# RMP_MAIN_ZERO.net
KiCad netlist of a schematic drawn in Altium Designer
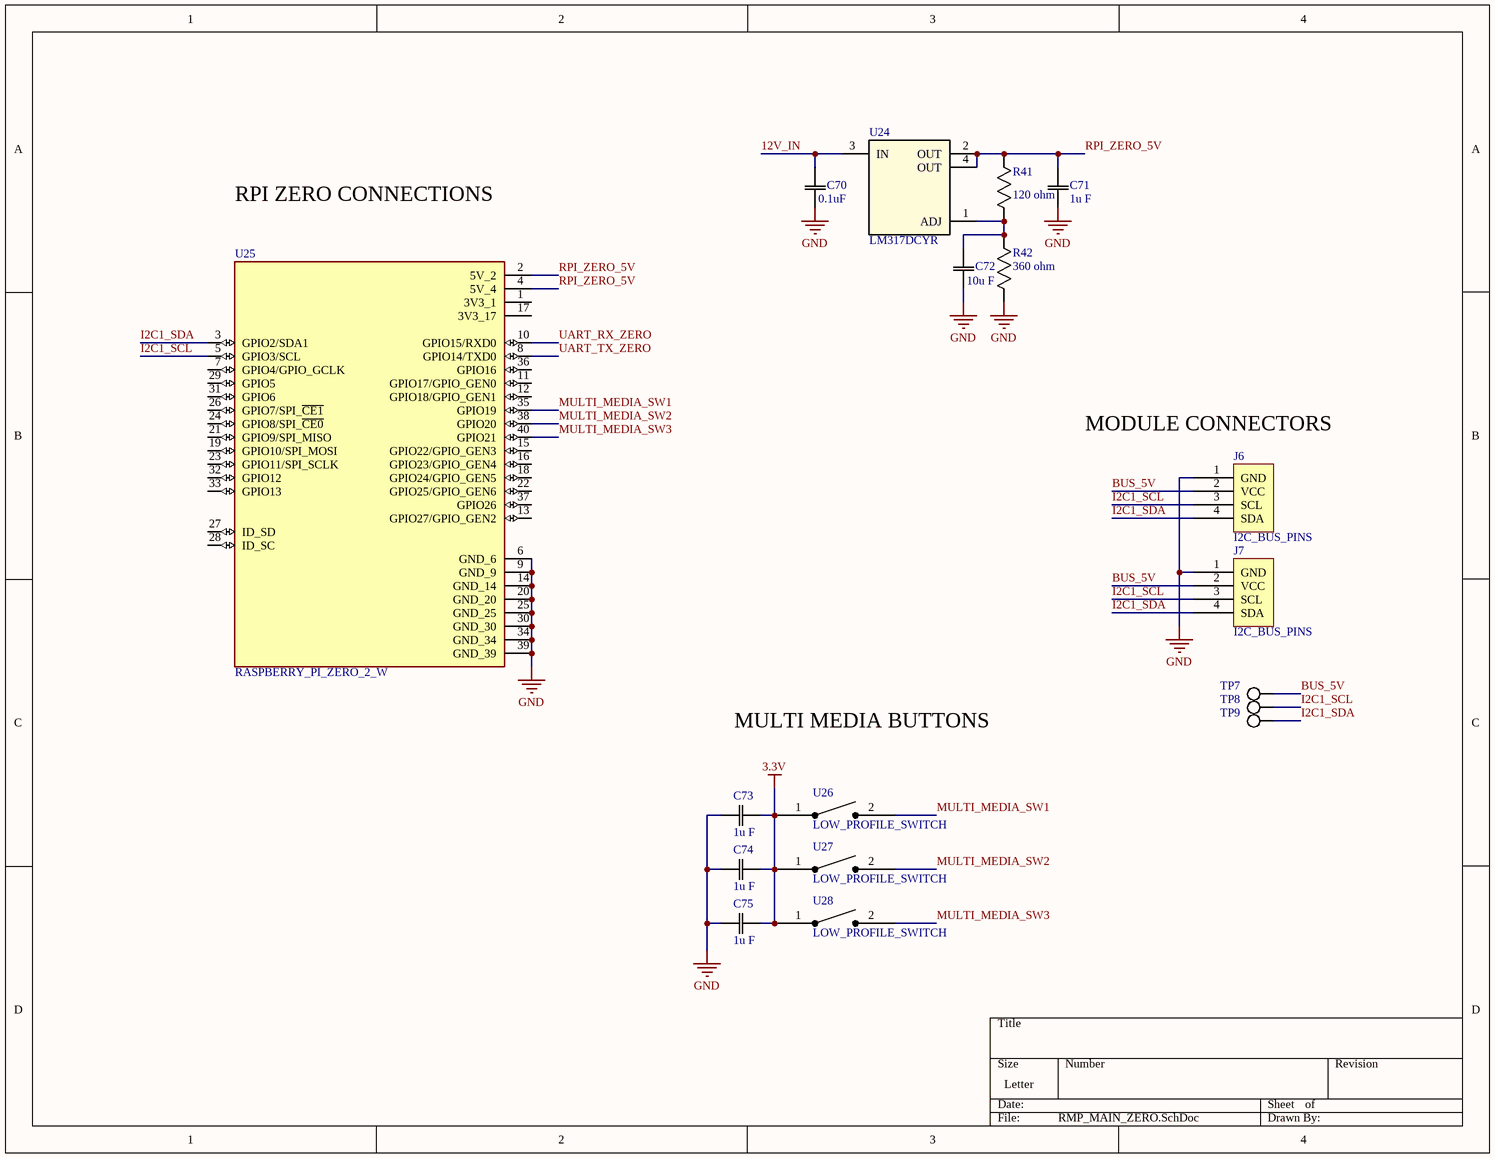
[diagram p0: RMP_MAIN_ZERO.SchDoc]

(export (version "E")
  (design (tool "Eeschema 10.0.6"))
  (components
    (comp (ref "C70")
      (value "0.1uF")
      (footprint "CC0805N_YAG-M")
      (description "0.1 µF ±10% 50V Ceramic Capacitor X7R 0805 (2012 Metric)")
      (fields (field (name "Comment") "CC0805KRX7R9BB104"))
      (libsource (lib "Schlib1") (part "CAP_CC0805KRX7R9BB104"))
    )
    (comp (ref "C71")
      (value "1u F")
      (footprint "CAP_CL21B105KAFNNNE_SAM-M")
      (description "1 µF ±10% 25V Ceramic Capacitor X7R 0805 (2012 Metric)")
      (fields (field (name "Comment") "CL21B105KAFNNNE"))
      (libsource (lib "Schlib1") (part "CAP_CL21B105KAFNNNE"))
    )
    (comp (ref "C72")
      (value "10u F")
      (footprint "G-21_MUR-M")
      (description "10 µF ±10% 16V Ceramic Capacitor X5R 0805 (2012 Metric)")
      (fields (field (name "Comment") "GRM21BR61C106KE15K"))
      (libsource (lib "Schlib1") (part "CAP_GRM21BR61C106KE15K"))
    )
    (comp (ref "C73")
      (value "1u F")
      (footprint "CAP_CL21B105KAFNNNE_SAM-M")
      (description "1 µF ±10% 25V Ceramic Capacitor X7R 0805 (2012 Metric)")
      (fields (field (name "Comment") "CL21B105KAFNNNE"))
      (libsource (lib "Schlib1") (part "CAP_CL21B105KAFNNNE"))
    )
    (comp (ref "C74")
      (value "1u F")
      (footprint "CAP_CL21B105KAFNNNE_SAM-M")
      (description "1 µF ±10% 25V Ceramic Capacitor X7R 0805 (2012 Metric)")
      (fields (field (name "Comment") "CL21B105KAFNNNE"))
      (libsource (lib "Schlib1") (part "CAP_CL21B105KAFNNNE"))
    )
    (comp (ref "C75")
      (value "1u F")
      (footprint "CAP_CL21B105KAFNNNE_SAM-M")
      (description "1 µF ±10% 25V Ceramic Capacitor X7R 0805 (2012 Metric)")
      (fields (field (name "Comment") "CL21B105KAFNNNE"))
      (libsource (lib "Schlib1") (part "CAP_CL21B105KAFNNNE"))
    )
    (comp (ref "J6")
      (value "I2C_BUS_PINS")
      (footprint "4 PIN HEADER")
      (libsource (lib "Schlib1") (part "I2C_BUS_PINS"))
    )
    (comp (ref "J7")
      (value "I2C_BUS_PINS")
      (footprint "4 PIN HEADER")
      (libsource (lib "Schlib1") (part "I2C_BUS_PINS"))
    )
    (comp (ref "R41")
      (value "120 ohm")
      (footprint "RES_RNCF0805_STP-M")
      (description "120 Ohms ±0.5% 0.25W, 1/4W Chip Resistor 0805 (2012 Metric) Automotive AEC-Q200 Thin Film")
      (fields (field (name "Comment") "RNCF0805DTE120R"))
      (libsource (lib "Schlib1") (part "RES_RNCF0805DTE120R"))
    )
    (comp (ref "R42")
      (value "360 ohm")
      (footprint "RES_RNCF0805_STP-M")
      (description "360 Ohms ±0.5% 0.25W, 1/4W Chip Resistor 0805 (2012 Metric) Automotive AEC-Q200 Thin Film")
      (fields (field (name "Comment") "RNCF0805DTE360R"))
      (libsource (lib "Schlib1") (part "RES_RNCF0805DTE360R"))
    )
    (comp (ref "TP7")
      (value "TestPoint")
      (footprint "Testpoint")
      (libsource (lib "Schlib1") (part "TestPoint"))
    )
    (comp (ref "TP8")
      (value "TestPoint")
      (footprint "Testpoint")
      (libsource (lib "Schlib1") (part "TestPoint"))
    )
    (comp (ref "TP9")
      (value "TestPoint")
      (footprint "Testpoint")
      (libsource (lib "Schlib1") (part "TestPoint"))
    )
    (comp (ref "U24")
      (value "LM317DCYR")
      (footprint "DCY0004A_M")
      (description "Linear Voltage Regulator IC Positive Adjustable 1 Output 1.5A SOT-223-4")
      (fields
        (field (name "ALTERNATE_PARTNUMBER") "LM317DCY")
        (field (name "MANUFACTURER") "Texas Instruments")
        (field (name "SYMBOLCREATER") "Altium")
      )
      (libsource (lib "Schlib1") (part "LM317DCYR"))
    )
    (comp (ref "U25")
      (value "RASPBERRY_PI_ZERO_2_W")
      (footprint "MODULE_RASPBERRY_PI_ZERO_2_W")
      (fields (field (name "MF") "Raspberry Pi") (field (name "MP") "RASPBERRY PI ZERO 2 W"))
      (libsource (lib "Schlib1") (part "RASPBERRY_PI_ZERO_2_W"))
    )
    (comp (ref "U26")
      (value "LOW_PROFILE_SWITCH")
      (footprint "2PINHEADER")
      (description "connector for low profile mechanical switch")
      (libsource (lib "Schlib1") (part "LOW_PROFILE_SWITCH"))
    )
    (comp (ref "U27")
      (value "LOW_PROFILE_SWITCH")
      (footprint "2PINHEADER")
      (description "connector for low profile mechanical switch")
      (libsource (lib "Schlib1") (part "LOW_PROFILE_SWITCH"))
    )
    (comp (ref "U28")
      (value "LOW_PROFILE_SWITCH")
      (footprint "2PINHEADER")
      (description "connector for low profile mechanical switch")
      (libsource (lib "Schlib1") (part "LOW_PROFILE_SWITCH"))
    )
  )
  (nets
    (net (code "1") (name "/12V_IN") (class "Default")
      (node (ref "C70") (pin "2") (pinfunction "2_2") (pintype "passive"))
      (node (ref "U24") (pin "3") (pinfunction "IN_3") (pintype "power_in"))
    )
    (net (code "2") (name "/BUS_5V") (class "Default")
      (node (ref "J6") (pin "2") (pinfunction "VCC_2") (pintype "passive"))
      (node (ref "J7") (pin "2") (pinfunction "VCC_2") (pintype "passive"))
      (node (ref "TP7") (pin "1") (pinfunction "1_1") (pintype "passive"))
    )
    (net (code "3") (name "/I2C1_SCL") (class "Default")
      (node (ref "J6") (pin "3") (pinfunction "SCL_3") (pintype "passive"))
      (node (ref "J7") (pin "3") (pinfunction "SCL_3") (pintype "passive"))
      (node (ref "TP8") (pin "1") (pinfunction "1_1") (pintype "passive"))
      (node (ref "U25") (pin "5") (pinfunction "GPIO3/SCL_5") (pintype "bidirectional"))
    )
    (net (code "4") (name "/I2C1_SDA") (class "Default")
      (node (ref "J6") (pin "4") (pinfunction "SDA_4") (pintype "passive"))
      (node (ref "J7") (pin "4") (pinfunction "SDA_4") (pintype "passive"))
      (node (ref "TP9") (pin "1") (pinfunction "1_1") (pintype "passive"))
      (node (ref "U25") (pin "3") (pinfunction "GPIO2/SDA1_3") (pintype "bidirectional"))
    )
    (net (code "5") (name "/MULTI_MEDIA_SW1") (class "Default")
      (node (ref "U25") (pin "35") (pinfunction "GPIO19_35") (pintype "bidirectional"))
      (node (ref "U26") (pin "2") (pinfunction "2_2") (pintype "passive"))
    )
    (net (code "6") (name "/MULTI_MEDIA_SW2") (class "Default")
      (node (ref "U25") (pin "38") (pinfunction "GPIO20_38") (pintype "bidirectional"))
      (node (ref "U27") (pin "2") (pinfunction "2_2") (pintype "passive"))
    )
    (net (code "7") (name "/MULTI_MEDIA_SW3") (class "Default")
      (node (ref "U25") (pin "40") (pinfunction "GPIO21_40") (pintype "bidirectional"))
      (node (ref "U28") (pin "2") (pinfunction "2_2") (pintype "passive"))
    )
    (net (code "8") (name "/RPI_ZERO_5V") (class "Default")
      (node (ref "C71") (pin "2") (pinfunction "2_2") (pintype "passive"))
      (node (ref "R41") (pin "2") (pinfunction "2_2") (pintype "passive"))
      (node (ref "U24") (pin "2") (pinfunction "OUT_2") (pintype "power_in"))
      (node (ref "U24") (pin "4") (pinfunction "OUT_4") (pintype "power_in"))
      (node (ref "U25") (pin "2") (pinfunction "5V_2_2") (pintype "power_in"))
      (node (ref "U25") (pin "4") (pinfunction "5V_4_4") (pintype "power_in"))
    )
    (net (code "9") (name "/UART_RX_ZERO") (class "Default")
      (node (ref "U25") (pin "10") (pinfunction "GPIO15/RXD0_10") (pintype "bidirectional"))
    )
    (net (code "10") (name "/UART_TX_ZERO") (class "Default")
      (node (ref "U25") (pin "8") (pinfunction "GPIO14/TXD0_8") (pintype "bidirectional"))
    )
    (net (code "11") (name "3.3V") (class "Default")
      (node (ref "C73") (pin "1") (pinfunction "1_1") (pintype "passive"))
      (node (ref "C74") (pin "1") (pinfunction "1_1") (pintype "passive"))
      (node (ref "C75") (pin "1") (pinfunction "1_1") (pintype "passive"))
      (node (ref "U26") (pin "1") (pinfunction "1_1") (pintype "passive"))
      (node (ref "U27") (pin "1") (pinfunction "1_1") (pintype "passive"))
      (node (ref "U28") (pin "1") (pinfunction "1_1") (pintype "passive"))
    )
    (net (code "12") (name "GND") (class "Default")
      (node (ref "C70") (pin "1") (pinfunction "1_1") (pintype "passive"))
      (node (ref "C71") (pin "1") (pinfunction "1_1") (pintype "passive"))
      (node (ref "C72") (pin "1") (pinfunction "1_1") (pintype "passive"))
      (node (ref "C73") (pin "2") (pinfunction "2_2") (pintype "passive"))
      (node (ref "C74") (pin "2") (pinfunction "2_2") (pintype "passive"))
      (node (ref "C75") (pin "2") (pinfunction "2_2") (pintype "passive"))
      (node (ref "J6") (pin "1") (pinfunction "GND_1") (pintype "passive"))
      (node (ref "J7") (pin "1") (pinfunction "GND_1") (pintype "passive"))
      (node (ref "R42") (pin "1") (pinfunction "1_1") (pintype "passive"))
      (node (ref "U25") (pin "14") (pinfunction "GND_14_14") (pintype "power_in"))
      (node (ref "U25") (pin "20") (pinfunction "GND_20_20") (pintype "power_in"))
      (node (ref "U25") (pin "25") (pinfunction "GND_25_25") (pintype "power_in"))
      (node (ref "U25") (pin "30") (pinfunction "GND_30_30") (pintype "power_in"))
      (node (ref "U25") (pin "34") (pinfunction "GND_34_34") (pintype "power_in"))
      (node (ref "U25") (pin "39") (pinfunction "GND_39_39") (pintype "power_in"))
      (node (ref "U25") (pin "6") (pinfunction "GND_6_6") (pintype "power_in"))
      (node (ref "U25") (pin "9") (pinfunction "GND_9_9") (pintype "power_in"))
    )
    (net (code "13") (name "Net-(U24-ADJ)") (class "Default")
      (node (ref "C72") (pin "2") (pinfunction "2_2") (pintype "passive"))
      (node (ref "R41") (pin "1") (pinfunction "1_1") (pintype "passive"))
      (node (ref "R42") (pin "2") (pinfunction "2_2") (pintype "passive"))
      (node (ref "U24") (pin "1") (pinfunction "ADJ_1") (pintype "power_in"))
    )
    (net (code "14") (name "unconnected-(U25-3V3_1-Pad1)") (class "Default")
      (node (ref "U25") (pin "1") (pinfunction "3V3_1_1") (pintype "power_in"))
    )
    (net (code "15") (name "unconnected-(U25-3V3_17-Pad17)") (class "Default")
      (node (ref "U25") (pin "17") (pinfunction "3V3_17_17") (pintype "power_in"))
    )
    (net (code "16") (name "unconnected-(U25-GPIO4{slash}GPIO_GCLK-Pad7)") (class "Default")
      (node (ref "U25") (pin "7") (pinfunction "GPIO4/GPIO_GCLK_7") (pintype "bidirectional"))
    )
    (net (code "17") (name "unconnected-(U25-GPIO5-Pad29)") (class "Default")
      (node (ref "U25") (pin "29") (pinfunction "GPIO5_29") (pintype "bidirectional"))
    )
    (net (code "18") (name "unconnected-(U25-GPIO6-Pad31)") (class "Default")
      (node (ref "U25") (pin "31") (pinfunction "GPIO6_31") (pintype "bidirectional"))
    )
    (net (code "19") (name "unconnected-(U25-GPIO7{slash}SPI_~{CE1}-Pad26)") (class "Default")
      (node (ref "U25") (pin "26") (pinfunction "GPIO7/SPI_~{CE1}_26") (pintype "bidirectional"))
    )
    (net (code "20") (name "unconnected-(U25-GPIO8{slash}SPI_~{CE0}-Pad24)") (class "Default")
      (node (ref "U25") (pin "24") (pinfunction "GPIO8/SPI_~{CE0}_24") (pintype "bidirectional"))
    )
    (net (code "21") (name "unconnected-(U25-GPIO9{slash}SPI_MISO-Pad21)") (class "Default")
      (node (ref "U25") (pin "21") (pinfunction "GPIO9/SPI_MISO_21") (pintype "bidirectional"))
    )
    (net (code "22") (name "unconnected-(U25-GPIO10{slash}SPI_MOSI-Pad19)") (class "Default")
      (node (ref "U25") (pin "19") (pinfunction "GPIO10/SPI_MOSI_19") (pintype "bidirectional"))
    )
    (net (code "23") (name "unconnected-(U25-GPIO11{slash}SPI_SCLK-Pad23)") (class "Default")
      (node (ref "U25") (pin "23") (pinfunction "GPIO11/SPI_SCLK_23") (pintype "bidirectional"))
    )
    (net (code "24") (name "unconnected-(U25-GPIO12-Pad32)") (class "Default")
      (node (ref "U25") (pin "32") (pinfunction "GPIO12_32") (pintype "bidirectional"))
    )
    (net (code "25") (name "unconnected-(U25-GPIO13-Pad33)") (class "Default")
      (node (ref "U25") (pin "33") (pinfunction "GPIO13_33") (pintype "bidirectional"))
    )
    (net (code "26") (name "unconnected-(U25-GPIO16-Pad36)") (class "Default")
      (node (ref "U25") (pin "36") (pinfunction "GPIO16_36") (pintype "bidirectional"))
    )
    (net (code "27") (name "unconnected-(U25-GPIO17{slash}GPIO_GEN0-Pad11)") (class "Default")
      (node (ref "U25") (pin "11") (pinfunction "GPIO17/GPIO_GEN0_11") (pintype "bidirectional"))
    )
    (net (code "28") (name "unconnected-(U25-GPIO18{slash}GPIO_GEN1-Pad12)") (class "Default")
      (node (ref "U25") (pin "12") (pinfunction "GPIO18/GPIO_GEN1_12") (pintype "bidirectional"))
    )
    (net (code "29") (name "unconnected-(U25-GPIO22{slash}GPIO_GEN3-Pad15)") (class "Default")
      (node (ref "U25") (pin "15") (pinfunction "GPIO22/GPIO_GEN3_15") (pintype "bidirectional"))
    )
    (net (code "30") (name "unconnected-(U25-GPIO23{slash}GPIO_GEN4-Pad16)") (class "Default")
      (node (ref "U25") (pin "16") (pinfunction "GPIO23/GPIO_GEN4_16") (pintype "bidirectional"))
    )
    (net (code "31") (name "unconnected-(U25-GPIO24{slash}GPIO_GEN5-Pad18)") (class "Default")
      (node (ref "U25") (pin "18") (pinfunction "GPIO24/GPIO_GEN5_18") (pintype "bidirectional"))
    )
    (net (code "32") (name "unconnected-(U25-GPIO25{slash}GPIO_GEN6-Pad22)") (class "Default")
      (node (ref "U25") (pin "22") (pinfunction "GPIO25/GPIO_GEN6_22") (pintype "bidirectional"))
    )
    (net (code "33") (name "unconnected-(U25-GPIO26-Pad37)") (class "Default")
      (node (ref "U25") (pin "37") (pinfunction "GPIO26_37") (pintype "bidirectional"))
    )
    (net (code "34") (name "unconnected-(U25-GPIO27{slash}GPIO_GEN2-Pad13)") (class "Default")
      (node (ref "U25") (pin "13") (pinfunction "GPIO27/GPIO_GEN2_13") (pintype "bidirectional"))
    )
    (net (code "35") (name "unconnected-(U25-ID_SC-Pad28)") (class "Default")
      (node (ref "U25") (pin "28") (pinfunction "ID_SC_28") (pintype "bidirectional"))
    )
    (net (code "36") (name "unconnected-(U25-ID_SD-Pad27)") (class "Default")
      (node (ref "U25") (pin "27") (pinfunction "ID_SD_27") (pintype "bidirectional"))
    )
  )
)
